# forever_flasher.net
KiCad netlist of a schematic drawn in EAGLE
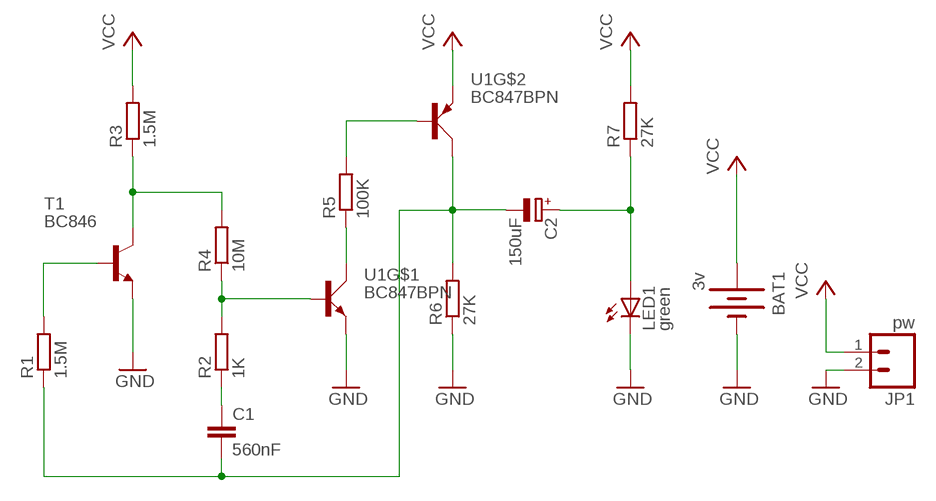
[diagram p0: schematic, sheet 1]

(export (version "E")
  (design (tool "Eeschema 10.0.6"))
  (components
    (comp (ref "BAT1")
      (value "3v")
      (footprint "eagle-import:BATTCON_12MM")
      (libsource (lib "eagle-import") (part "BATTERY12MM"))
    )
    (comp (ref "C1")
      (value "560nF")
      (footprint "eagle-import:C0805")
      (libsource (lib "eagle-import") (part "C-EUC0805"))
    )
    (comp (ref "C2")
      (value "150uF")
      (footprint "eagle-import:CT7343")
      (libsource (lib "eagle-import") (part "CPOL-EUCT7343"))
    )
    (comp (ref "JP1")
      (value "pw")
      (footprint "eagle-import:1X02")
      (libsource (lib "eagle-import") (part "M02PTH"))
    )
    (comp (ref "LED1")
      (value "green")
      (footprint "eagle-import:CHIPLED_0805")
      (libsource (lib "eagle-import") (part "LEDCHIPLED_0805"))
    )
    (comp (ref "R1")
      (value "1.5M")
      (footprint "eagle-import:R0805")
      (libsource (lib "eagle-import") (part "R-EU_R0805"))
    )
    (comp (ref "R2")
      (value "1K")
      (footprint "eagle-import:R0805")
      (libsource (lib "eagle-import") (part "R-EU_R0805"))
    )
    (comp (ref "R3")
      (value "1.5M")
      (footprint "eagle-import:R0805")
      (libsource (lib "eagle-import") (part "R-EU_R0805"))
    )
    (comp (ref "R4")
      (value "10M")
      (footprint "eagle-import:R0805")
      (libsource (lib "eagle-import") (part "R-EU_R0805"))
    )
    (comp (ref "R5")
      (value "100K")
      (footprint "eagle-import:R0805")
      (libsource (lib "eagle-import") (part "R-EU_R0805"))
    )
    (comp (ref "R6")
      (value "27K")
      (footprint "eagle-import:R0805")
      (libsource (lib "eagle-import") (part "R-EU_R0805"))
    )
    (comp (ref "R7")
      (value "27K")
      (footprint "eagle-import:R0805")
      (libsource (lib "eagle-import") (part "R-EU_R0805"))
    )
    (comp (ref "T1")
      (value "BC846")
      (footprint "eagle-import:SOT23")
      (libsource (lib "eagle-import") (part "BC846"))
    )
    (comp (ref "U1")
      (value "BC847BPN")
      (footprint "eagle-import:SOT363_PHILIPS")
      (libsource (lib "eagle-import") (part "BC847BPN{dblquote}"))
    )
  )
  (nets
    (net (code "1") (name "GND") (class "Default")
      (node (ref "BAT1") (pin "GND") (pinfunction "-_GND") (pintype "power_in"))
      (node (ref "JP1") (pin "2") (pinfunction "2_2") (pintype "passive"))
      (node (ref "LED1") (pin "C") (pinfunction "C_C") (pintype "passive"))
      (node (ref "R6") (pin "1") (pinfunction "1_1") (pintype "passive"))
      (node (ref "T1") (pin "2") (pinfunction "E_2") (pintype "passive"))
      (node (ref "U1") (pin "1") (pinfunction "E_1") (pintype "passive"))
    )
    (net (code "2") (name "Net-(C1-Pad1)") (class "Default")
      (node (ref "C1") (pin "1") (pinfunction "1_1") (pintype "passive"))
      (node (ref "R2") (pin "1") (pinfunction "1_1") (pintype "passive"))
    )
    (net (code "3") (name "Net-(C2-Pad+)") (class "Default")
      (node (ref "C2") (pin "+") (pinfunction "+_+") (pintype "passive"))
      (node (ref "LED1") (pin "A") (pinfunction "A_A") (pintype "passive"))
      (node (ref "R7") (pin "1") (pinfunction "1_1") (pintype "passive"))
    )
    (net (code "4") (name "Net-(T1-B)") (class "Default")
      (node (ref "R1") (pin "2") (pinfunction "2_2") (pintype "passive"))
      (node (ref "T1") (pin "1") (pinfunction "B_1") (pintype "passive"))
    )
    (net (code "5") (name "Net-(T1-C)") (class "Default")
      (node (ref "R3") (pin "1") (pinfunction "1_1") (pintype "passive"))
      (node (ref "R4") (pin "2") (pinfunction "2_2") (pintype "passive"))
      (node (ref "T1") (pin "3") (pinfunction "C_3") (pintype "passive"))
    )
    (net (code "6") (name "Net-(U1A-B)") (class "Default")
      (node (ref "R2") (pin "2") (pinfunction "2_2") (pintype "passive"))
      (node (ref "R4") (pin "1") (pinfunction "1_1") (pintype "passive"))
      (node (ref "U1") (pin "2") (pinfunction "B_2") (pintype "passive"))
    )
    (net (code "7") (name "Net-(U1A-C)") (class "Default")
      (node (ref "R5") (pin "1") (pinfunction "1_1") (pintype "passive"))
      (node (ref "U1") (pin "6") (pinfunction "C_6") (pintype "passive"))
    )
    (net (code "8") (name "Net-(U1B-B)") (class "Default")
      (node (ref "R5") (pin "2") (pinfunction "2_2") (pintype "passive"))
      (node (ref "U1") (pin "5") (pinfunction "B_5") (pintype "passive"))
    )
    (net (code "9") (name "Net-(U1B-C)") (class "Default")
      (node (ref "C1") (pin "2") (pinfunction "2_2") (pintype "passive"))
      (node (ref "C2") (pin "-") (pinfunction "-_-") (pintype "passive"))
      (node (ref "R1") (pin "1") (pinfunction "1_1") (pintype "passive"))
      (node (ref "R6") (pin "2") (pinfunction "2_2") (pintype "passive"))
      (node (ref "U1") (pin "3") (pinfunction "C_3") (pintype "passive"))
    )
    (net (code "10") (name "VCC") (class "Default")
      (node (ref "BAT1") (pin "PWR@1") (pinfunction "+_PWR@1") (pintype "power_in"))
      (node (ref "JP1") (pin "1") (pinfunction "1_1") (pintype "passive"))
      (node (ref "R3") (pin "2") (pinfunction "2_2") (pintype "passive"))
      (node (ref "R7") (pin "2") (pinfunction "2_2") (pintype "passive"))
      (node (ref "U1") (pin "4") (pinfunction "E_4") (pintype "passive"))
    )
  )
)
